# 05-ModuleControls.net
KiCad netlist of a schematic drawn in Altium Designer
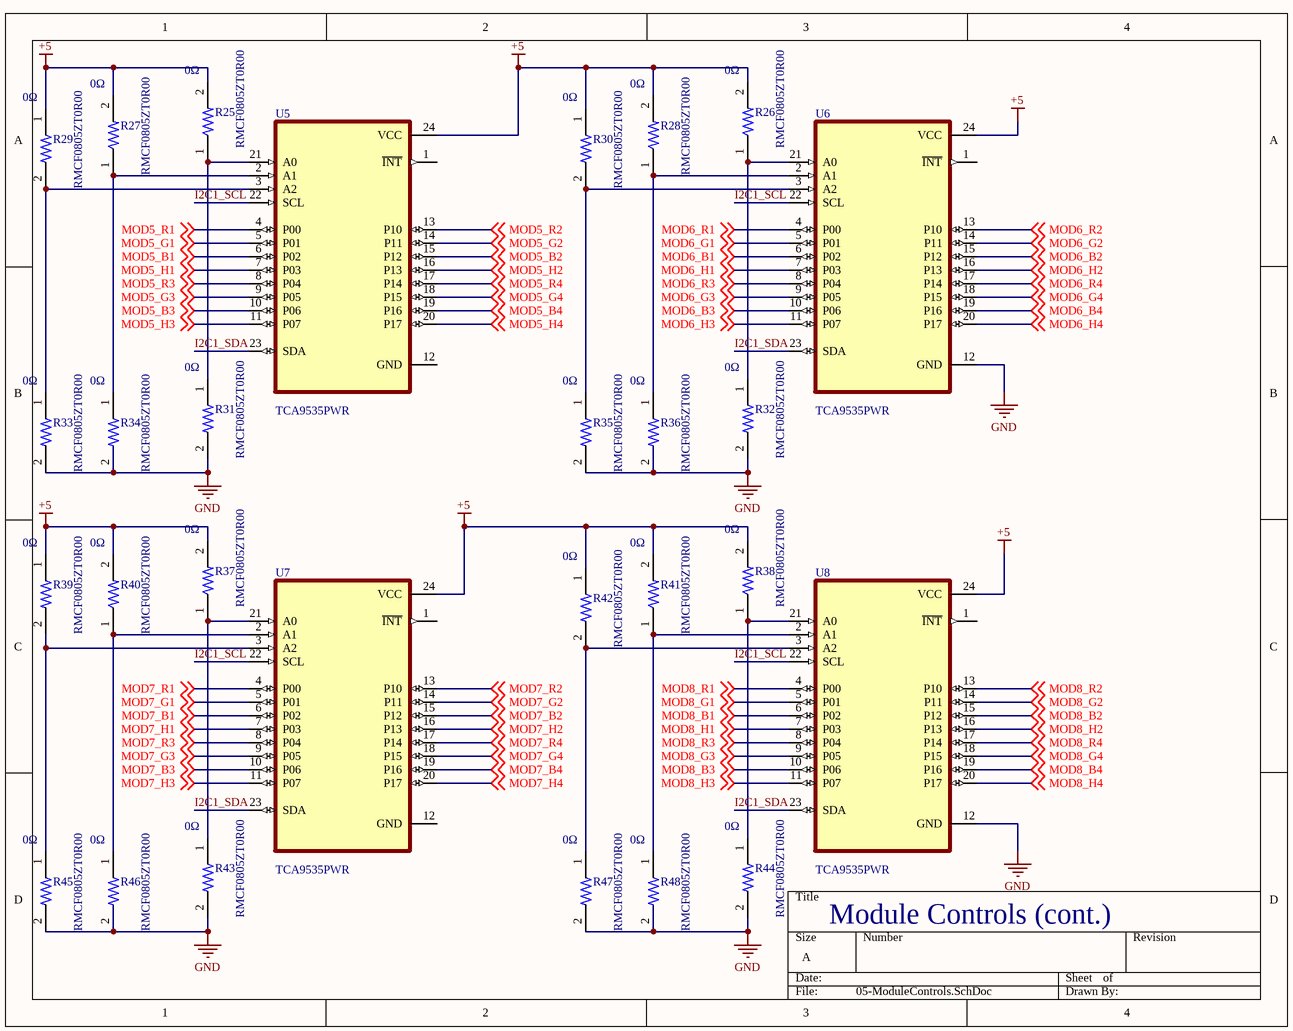
[diagram p0: 05-ModuleControls.SchDoc]

(export (version "E")
  (design (tool "Eeschema 10.0.6"))
  (components
    (comp (ref "R25")
      (value "RMCF0805ZT0R00")
      (footprint "RESC2012X60N")
      (description "0 Ohms Jumper 0.125W, 1/8W Chip Resistor 0805 (2012 Metric) Automotive AEC-Q200 Thick Film")
      (fields (field (name "MF") "Stackpole Electronics") (field (name "RESITANCE") "0Ω"))
      (libsource (lib "base-board") (part "RMCF0805ZT0R00"))
    )
    (comp (ref "R26")
      (value "RMCF0805ZT0R00")
      (footprint "RESC2012X60N")
      (description "0 Ohms Jumper 0.125W, 1/8W Chip Resistor 0805 (2012 Metric) Automotive AEC-Q200 Thick Film")
      (fields (field (name "MF") "Stackpole Electronics") (field (name "RESITANCE") "0Ω"))
      (libsource (lib "base-board") (part "RMCF0805ZT0R00"))
    )
    (comp (ref "R27")
      (value "RMCF0805ZT0R00")
      (footprint "RESC2012X60N")
      (description "0 Ohms Jumper 0.125W, 1/8W Chip Resistor 0805 (2012 Metric) Automotive AEC-Q200 Thick Film")
      (fields (field (name "MF") "Stackpole Electronics") (field (name "RESITANCE") "0Ω"))
      (libsource (lib "base-board") (part "RMCF0805ZT0R00"))
    )
    (comp (ref "R28")
      (value "RMCF0805ZT0R00")
      (footprint "RESC2012X60N")
      (description "0 Ohms Jumper 0.125W, 1/8W Chip Resistor 0805 (2012 Metric) Automotive AEC-Q200 Thick Film")
      (fields (field (name "MF") "Stackpole Electronics") (field (name "RESITANCE") "0Ω"))
      (libsource (lib "base-board") (part "RMCF0805ZT0R00"))
    )
    (comp (ref "R29")
      (value "RMCF0805ZT0R00")
      (footprint "RESC2012X60N")
      (description "0 Ohms Jumper 0.125W, 1/8W Chip Resistor 0805 (2012 Metric) Automotive AEC-Q200 Thick Film")
      (fields (field (name "MF") "Stackpole Electronics") (field (name "RESITANCE") "0Ω"))
      (libsource (lib "base-board") (part "RMCF0805ZT0R00"))
    )
    (comp (ref "R30")
      (value "RMCF0805ZT0R00")
      (footprint "RESC2012X60N")
      (description "0 Ohms Jumper 0.125W, 1/8W Chip Resistor 0805 (2012 Metric) Automotive AEC-Q200 Thick Film")
      (fields (field (name "MF") "Stackpole Electronics") (field (name "RESITANCE") "0Ω"))
      (libsource (lib "base-board") (part "RMCF0805ZT0R00"))
    )
    (comp (ref "R31")
      (value "RMCF0805ZT0R00")
      (footprint "RESC2012X60N")
      (description "0 Ohms Jumper 0.125W, 1/8W Chip Resistor 0805 (2012 Metric) Automotive AEC-Q200 Thick Film")
      (fields (field (name "MF") "Stackpole Electronics") (field (name "RESITANCE") "0Ω"))
      (libsource (lib "base-board") (part "RMCF0805ZT0R00"))
    )
    (comp (ref "R32")
      (value "RMCF0805ZT0R00")
      (footprint "RESC2012X60N")
      (description "0 Ohms Jumper 0.125W, 1/8W Chip Resistor 0805 (2012 Metric) Automotive AEC-Q200 Thick Film")
      (fields (field (name "MF") "Stackpole Electronics") (field (name "RESITANCE") "0Ω"))
      (libsource (lib "base-board") (part "RMCF0805ZT0R00"))
    )
    (comp (ref "R33")
      (value "RMCF0805ZT0R00")
      (footprint "RESC2012X60N")
      (description "0 Ohms Jumper 0.125W, 1/8W Chip Resistor 0805 (2012 Metric) Automotive AEC-Q200 Thick Film")
      (fields (field (name "MF") "Stackpole Electronics") (field (name "RESITANCE") "0Ω"))
      (libsource (lib "base-board") (part "RMCF0805ZT0R00"))
    )
    (comp (ref "R34")
      (value "RMCF0805ZT0R00")
      (footprint "RESC2012X60N")
      (description "0 Ohms Jumper 0.125W, 1/8W Chip Resistor 0805 (2012 Metric) Automotive AEC-Q200 Thick Film")
      (fields (field (name "MF") "Stackpole Electronics") (field (name "RESITANCE") "0Ω"))
      (libsource (lib "base-board") (part "RMCF0805ZT0R00"))
    )
    (comp (ref "R35")
      (value "RMCF0805ZT0R00")
      (footprint "RESC2012X60N")
      (description "0 Ohms Jumper 0.125W, 1/8W Chip Resistor 0805 (2012 Metric) Automotive AEC-Q200 Thick Film")
      (fields (field (name "MF") "Stackpole Electronics") (field (name "RESITANCE") "0Ω"))
      (libsource (lib "base-board") (part "RMCF0805ZT0R00"))
    )
    (comp (ref "R36")
      (value "RMCF0805ZT0R00")
      (footprint "RESC2012X60N")
      (description "0 Ohms Jumper 0.125W, 1/8W Chip Resistor 0805 (2012 Metric) Automotive AEC-Q200 Thick Film")
      (fields (field (name "MF") "Stackpole Electronics") (field (name "RESITANCE") "0Ω"))
      (libsource (lib "base-board") (part "RMCF0805ZT0R00"))
    )
    (comp (ref "R37")
      (value "RMCF0805ZT0R00")
      (footprint "RESC2012X60N")
      (description "0 Ohms Jumper 0.125W, 1/8W Chip Resistor 0805 (2012 Metric) Automotive AEC-Q200 Thick Film")
      (fields (field (name "MF") "Stackpole Electronics") (field (name "RESITANCE") "0Ω"))
      (libsource (lib "base-board") (part "RMCF0805ZT0R00"))
    )
    (comp (ref "R38")
      (value "RMCF0805ZT0R00")
      (footprint "RESC2012X60N")
      (description "0 Ohms Jumper 0.125W, 1/8W Chip Resistor 0805 (2012 Metric) Automotive AEC-Q200 Thick Film")
      (fields (field (name "MF") "Stackpole Electronics") (field (name "RESITANCE") "0Ω"))
      (libsource (lib "base-board") (part "RMCF0805ZT0R00"))
    )
    (comp (ref "R39")
      (value "RMCF0805ZT0R00")
      (footprint "RESC2012X60N")
      (description "0 Ohms Jumper 0.125W, 1/8W Chip Resistor 0805 (2012 Metric) Automotive AEC-Q200 Thick Film")
      (fields (field (name "MF") "Stackpole Electronics") (field (name "RESITANCE") "0Ω"))
      (libsource (lib "base-board") (part "RMCF0805ZT0R00"))
    )
    (comp (ref "R40")
      (value "RMCF0805ZT0R00")
      (footprint "RESC2012X60N")
      (description "0 Ohms Jumper 0.125W, 1/8W Chip Resistor 0805 (2012 Metric) Automotive AEC-Q200 Thick Film")
      (fields (field (name "MF") "Stackpole Electronics") (field (name "RESITANCE") "0Ω"))
      (libsource (lib "base-board") (part "RMCF0805ZT0R00"))
    )
    (comp (ref "R41")
      (value "RMCF0805ZT0R00")
      (footprint "RESC2012X60N")
      (description "0 Ohms Jumper 0.125W, 1/8W Chip Resistor 0805 (2012 Metric) Automotive AEC-Q200 Thick Film")
      (fields (field (name "MF") "Stackpole Electronics") (field (name "RESITANCE") "0Ω"))
      (libsource (lib "base-board") (part "RMCF0805ZT0R00"))
    )
    (comp (ref "R42")
      (value "RMCF0805ZT0R00")
      (footprint "RESC2012X60N")
      (description "0 Ohms Jumper 0.125W, 1/8W Chip Resistor 0805 (2012 Metric) Automotive AEC-Q200 Thick Film")
      (fields (field (name "MF") "Stackpole Electronics") (field (name "RESITANCE") "0Ω"))
      (libsource (lib "base-board") (part "RMCF0805ZT0R00"))
    )
    (comp (ref "R43")
      (value "RMCF0805ZT0R00")
      (footprint "RESC2012X60N")
      (description "0 Ohms Jumper 0.125W, 1/8W Chip Resistor 0805 (2012 Metric) Automotive AEC-Q200 Thick Film")
      (fields (field (name "MF") "Stackpole Electronics") (field (name "RESITANCE") "0Ω"))
      (libsource (lib "base-board") (part "RMCF0805ZT0R00"))
    )
    (comp (ref "R44")
      (value "RMCF0805ZT0R00")
      (footprint "RESC2012X60N")
      (description "0 Ohms Jumper 0.125W, 1/8W Chip Resistor 0805 (2012 Metric) Automotive AEC-Q200 Thick Film")
      (fields (field (name "MF") "Stackpole Electronics") (field (name "RESITANCE") "0Ω"))
      (libsource (lib "base-board") (part "RMCF0805ZT0R00"))
    )
    (comp (ref "R45")
      (value "RMCF0805ZT0R00")
      (footprint "RESC2012X60N")
      (description "0 Ohms Jumper 0.125W, 1/8W Chip Resistor 0805 (2012 Metric) Automotive AEC-Q200 Thick Film")
      (fields (field (name "MF") "Stackpole Electronics") (field (name "RESITANCE") "0Ω"))
      (libsource (lib "base-board") (part "RMCF0805ZT0R00"))
    )
    (comp (ref "R46")
      (value "RMCF0805ZT0R00")
      (footprint "RESC2012X60N")
      (description "0 Ohms Jumper 0.125W, 1/8W Chip Resistor 0805 (2012 Metric) Automotive AEC-Q200 Thick Film")
      (fields (field (name "MF") "Stackpole Electronics") (field (name "RESITANCE") "0Ω"))
      (libsource (lib "base-board") (part "RMCF0805ZT0R00"))
    )
    (comp (ref "R47")
      (value "RMCF0805ZT0R00")
      (footprint "RESC2012X60N")
      (description "0 Ohms Jumper 0.125W, 1/8W Chip Resistor 0805 (2012 Metric) Automotive AEC-Q200 Thick Film")
      (fields (field (name "MF") "Stackpole Electronics") (field (name "RESITANCE") "0Ω"))
      (libsource (lib "base-board") (part "RMCF0805ZT0R00"))
    )
    (comp (ref "R48")
      (value "RMCF0805ZT0R00")
      (footprint "RESC2012X60N")
      (description "0 Ohms Jumper 0.125W, 1/8W Chip Resistor 0805 (2012 Metric) Automotive AEC-Q200 Thick Film")
      (fields (field (name "MF") "Stackpole Electronics") (field (name "RESITANCE") "0Ω"))
      (libsource (lib "base-board") (part "RMCF0805ZT0R00"))
    )
    (comp (ref "U5")
      (value "TCA9535PWR")
      (footprint "SOP65P640X120-24N")
      (fields (field (name "MF") "Texas Instruments"))
      (libsource (lib "base-board") (part "TCA9535PWR"))
    )
    (comp (ref "U6")
      (value "TCA9535PWR")
      (footprint "SOP65P640X120-24N")
      (fields (field (name "MF") "Texas Instruments"))
      (libsource (lib "base-board") (part "TCA9535PWR"))
    )
    (comp (ref "U7")
      (value "TCA9535PWR")
      (footprint "SOP65P640X120-24N")
      (fields (field (name "MF") "Texas Instruments"))
      (libsource (lib "base-board") (part "TCA9535PWR"))
    )
    (comp (ref "U8")
      (value "TCA9535PWR")
      (footprint "SOP65P640X120-24N")
      (fields (field (name "MF") "Texas Instruments"))
      (libsource (lib "base-board") (part "TCA9535PWR"))
    )
  )
  (nets
    (net (code "1") (name "+5") (class "Default")
      (node (ref "R25") (pin "2") (pinfunction "2_2") (pintype "passive"))
      (node (ref "R26") (pin "2") (pinfunction "2_2") (pintype "passive"))
      (node (ref "R27") (pin "2") (pinfunction "2_2") (pintype "passive"))
      (node (ref "R28") (pin "2") (pinfunction "2_2") (pintype "passive"))
      (node (ref "R29") (pin "1") (pinfunction "1_1") (pintype "passive"))
      (node (ref "R30") (pin "1") (pinfunction "1_1") (pintype "passive"))
      (node (ref "R37") (pin "2") (pinfunction "2_2") (pintype "passive"))
      (node (ref "R38") (pin "2") (pinfunction "2_2") (pintype "passive"))
      (node (ref "R39") (pin "1") (pinfunction "1_1") (pintype "passive"))
      (node (ref "R40") (pin "2") (pinfunction "2_2") (pintype "passive"))
      (node (ref "R41") (pin "2") (pinfunction "2_2") (pintype "passive"))
      (node (ref "R42") (pin "1") (pinfunction "1_1") (pintype "passive"))
      (node (ref "U5") (pin "24") (pinfunction "VCC_24") (pintype "power_in"))
      (node (ref "U6") (pin "24") (pinfunction "VCC_24") (pintype "power_in"))
      (node (ref "U7") (pin "24") (pinfunction "VCC_24") (pintype "power_in"))
      (node (ref "U8") (pin "24") (pinfunction "VCC_24") (pintype "power_in"))
    )
    (net (code "2") (name "/I2C1_SCL") (class "Default")
      (node (ref "U5") (pin "22") (pinfunction "SCL_22") (pintype "input"))
      (node (ref "U6") (pin "22") (pinfunction "SCL_22") (pintype "input"))
      (node (ref "U7") (pin "22") (pinfunction "SCL_22") (pintype "input"))
      (node (ref "U8") (pin "22") (pinfunction "SCL_22") (pintype "input"))
    )
    (net (code "3") (name "/I2C1_SDA") (class "Default")
      (node (ref "U5") (pin "23") (pinfunction "SDA_23") (pintype "bidirectional"))
      (node (ref "U6") (pin "23") (pinfunction "SDA_23") (pintype "bidirectional"))
      (node (ref "U7") (pin "23") (pinfunction "SDA_23") (pintype "bidirectional"))
      (node (ref "U8") (pin "23") (pinfunction "SDA_23") (pintype "bidirectional"))
    )
    (net (code "4") (name "GND") (class "Default")
      (node (ref "R31") (pin "2") (pinfunction "2_2") (pintype "passive"))
      (node (ref "R32") (pin "2") (pinfunction "2_2") (pintype "passive"))
      (node (ref "R33") (pin "2") (pinfunction "2_2") (pintype "passive"))
      (node (ref "R34") (pin "2") (pinfunction "2_2") (pintype "passive"))
      (node (ref "R35") (pin "2") (pinfunction "2_2") (pintype "passive"))
      (node (ref "R36") (pin "2") (pinfunction "2_2") (pintype "passive"))
      (node (ref "R43") (pin "2") (pinfunction "2_2") (pintype "passive"))
      (node (ref "R44") (pin "2") (pinfunction "2_2") (pintype "passive"))
      (node (ref "R45") (pin "2") (pinfunction "2_2") (pintype "passive"))
      (node (ref "R46") (pin "2") (pinfunction "2_2") (pintype "passive"))
      (node (ref "R47") (pin "2") (pinfunction "2_2") (pintype "passive"))
      (node (ref "R48") (pin "2") (pinfunction "2_2") (pintype "passive"))
      (node (ref "U6") (pin "12") (pinfunction "GND_12") (pintype "power_in"))
      (node (ref "U8") (pin "12") (pinfunction "GND_12") (pintype "power_in"))
    )
    (net (code "5") (name "MOD5_B1") (class "Default")
      (node (ref "U5") (pin "6") (pinfunction "P02_6") (pintype "bidirectional"))
    )
    (net (code "6") (name "MOD5_B2") (class "Default")
      (node (ref "U5") (pin "15") (pinfunction "P12_15") (pintype "bidirectional"))
    )
    (net (code "7") (name "MOD5_B3") (class "Default")
      (node (ref "U5") (pin "10") (pinfunction "P06_10") (pintype "bidirectional"))
    )
    (net (code "8") (name "MOD5_B4") (class "Default")
      (node (ref "U5") (pin "19") (pinfunction "P16_19") (pintype "bidirectional"))
    )
    (net (code "9") (name "MOD5_G1") (class "Default")
      (node (ref "U5") (pin "5") (pinfunction "P01_5") (pintype "bidirectional"))
    )
    (net (code "10") (name "MOD5_G2") (class "Default")
      (node (ref "U5") (pin "14") (pinfunction "P11_14") (pintype "bidirectional"))
    )
    (net (code "11") (name "MOD5_G3") (class "Default")
      (node (ref "U5") (pin "9") (pinfunction "P05_9") (pintype "bidirectional"))
    )
    (net (code "12") (name "MOD5_G4") (class "Default")
      (node (ref "U5") (pin "18") (pinfunction "P15_18") (pintype "bidirectional"))
    )
    (net (code "13") (name "MOD5_H1") (class "Default")
      (node (ref "U5") (pin "7") (pinfunction "P03_7") (pintype "bidirectional"))
    )
    (net (code "14") (name "MOD5_H2") (class "Default")
      (node (ref "U5") (pin "16") (pinfunction "P13_16") (pintype "bidirectional"))
    )
    (net (code "15") (name "MOD5_H3") (class "Default")
      (node (ref "U5") (pin "11") (pinfunction "P07_11") (pintype "bidirectional"))
    )
    (net (code "16") (name "MOD5_H4") (class "Default")
      (node (ref "U5") (pin "20") (pinfunction "P17_20") (pintype "bidirectional"))
    )
    (net (code "17") (name "MOD5_R1") (class "Default")
      (node (ref "U5") (pin "4") (pinfunction "P00_4") (pintype "bidirectional"))
    )
    (net (code "18") (name "MOD5_R2") (class "Default")
      (node (ref "U5") (pin "13") (pinfunction "P10_13") (pintype "bidirectional"))
    )
    (net (code "19") (name "MOD5_R3") (class "Default")
      (node (ref "U5") (pin "8") (pinfunction "P04_8") (pintype "bidirectional"))
    )
    (net (code "20") (name "MOD5_R4") (class "Default")
      (node (ref "U5") (pin "17") (pinfunction "P14_17") (pintype "bidirectional"))
    )
    (net (code "21") (name "MOD6_B1") (class "Default")
      (node (ref "U6") (pin "6") (pinfunction "P02_6") (pintype "bidirectional"))
    )
    (net (code "22") (name "MOD6_B2") (class "Default")
      (node (ref "U6") (pin "15") (pinfunction "P12_15") (pintype "bidirectional"))
    )
    (net (code "23") (name "MOD6_B3") (class "Default")
      (node (ref "U6") (pin "10") (pinfunction "P06_10") (pintype "bidirectional"))
    )
    (net (code "24") (name "MOD6_B4") (class "Default")
      (node (ref "U6") (pin "19") (pinfunction "P16_19") (pintype "bidirectional"))
    )
    (net (code "25") (name "MOD6_G1") (class "Default")
      (node (ref "U6") (pin "5") (pinfunction "P01_5") (pintype "bidirectional"))
    )
    (net (code "26") (name "MOD6_G2") (class "Default")
      (node (ref "U6") (pin "14") (pinfunction "P11_14") (pintype "bidirectional"))
    )
    (net (code "27") (name "MOD6_G3") (class "Default")
      (node (ref "U6") (pin "9") (pinfunction "P05_9") (pintype "bidirectional"))
    )
    (net (code "28") (name "MOD6_G4") (class "Default")
      (node (ref "U6") (pin "18") (pinfunction "P15_18") (pintype "bidirectional"))
    )
    (net (code "29") (name "MOD6_H1") (class "Default")
      (node (ref "U6") (pin "7") (pinfunction "P03_7") (pintype "bidirectional"))
    )
    (net (code "30") (name "MOD6_H2") (class "Default")
      (node (ref "U6") (pin "16") (pinfunction "P13_16") (pintype "bidirectional"))
    )
    (net (code "31") (name "MOD6_H3") (class "Default")
      (node (ref "U6") (pin "11") (pinfunction "P07_11") (pintype "bidirectional"))
    )
    (net (code "32") (name "MOD6_H4") (class "Default")
      (node (ref "U6") (pin "20") (pinfunction "P17_20") (pintype "bidirectional"))
    )
    (net (code "33") (name "MOD6_R1") (class "Default")
      (node (ref "U6") (pin "4") (pinfunction "P00_4") (pintype "bidirectional"))
    )
    (net (code "34") (name "MOD6_R2") (class "Default")
      (node (ref "U6") (pin "13") (pinfunction "P10_13") (pintype "bidirectional"))
    )
    (net (code "35") (name "MOD6_R3") (class "Default")
      (node (ref "U6") (pin "8") (pinfunction "P04_8") (pintype "bidirectional"))
    )
    (net (code "36") (name "MOD6_R4") (class "Default")
      (node (ref "U6") (pin "17") (pinfunction "P14_17") (pintype "bidirectional"))
    )
    (net (code "37") (name "MOD7_B1") (class "Default")
      (node (ref "U7") (pin "6") (pinfunction "P02_6") (pintype "bidirectional"))
    )
    (net (code "38") (name "MOD7_B2") (class "Default")
      (node (ref "U7") (pin "15") (pinfunction "P12_15") (pintype "bidirectional"))
    )
    (net (code "39") (name "MOD7_B3") (class "Default")
      (node (ref "U7") (pin "10") (pinfunction "P06_10") (pintype "bidirectional"))
    )
    (net (code "40") (name "MOD7_B4") (class "Default")
      (node (ref "U7") (pin "19") (pinfunction "P16_19") (pintype "bidirectional"))
    )
    (net (code "41") (name "MOD7_G1") (class "Default")
      (node (ref "U7") (pin "5") (pinfunction "P01_5") (pintype "bidirectional"))
    )
    (net (code "42") (name "MOD7_G2") (class "Default")
      (node (ref "U7") (pin "14") (pinfunction "P11_14") (pintype "bidirectional"))
    )
    (net (code "43") (name "MOD7_G3") (class "Default")
      (node (ref "U7") (pin "9") (pinfunction "P05_9") (pintype "bidirectional"))
    )
    (net (code "44") (name "MOD7_G4") (class "Default")
      (node (ref "U7") (pin "18") (pinfunction "P15_18") (pintype "bidirectional"))
    )
    (net (code "45") (name "MOD7_H1") (class "Default")
      (node (ref "U7") (pin "7") (pinfunction "P03_7") (pintype "bidirectional"))
    )
    (net (code "46") (name "MOD7_H2") (class "Default")
      (node (ref "U7") (pin "16") (pinfunction "P13_16") (pintype "bidirectional"))
    )
    (net (code "47") (name "MOD7_H3") (class "Default")
      (node (ref "U7") (pin "11") (pinfunction "P07_11") (pintype "bidirectional"))
    )
    (net (code "48") (name "MOD7_H4") (class "Default")
      (node (ref "U7") (pin "20") (pinfunction "P17_20") (pintype "bidirectional"))
    )
    (net (code "49") (name "MOD7_R1") (class "Default")
      (node (ref "U7") (pin "4") (pinfunction "P00_4") (pintype "bidirectional"))
    )
    (net (code "50") (name "MOD7_R2") (class "Default")
      (node (ref "U7") (pin "13") (pinfunction "P10_13") (pintype "bidirectional"))
    )
    (net (code "51") (name "MOD7_R3") (class "Default")
      (node (ref "U7") (pin "8") (pinfunction "P04_8") (pintype "bidirectional"))
    )
    (net (code "52") (name "MOD7_R4") (class "Default")
      (node (ref "U7") (pin "17") (pinfunction "P14_17") (pintype "bidirectional"))
    )
    (net (code "53") (name "MOD8_B1") (class "Default")
      (node (ref "U8") (pin "6") (pinfunction "P02_6") (pintype "bidirectional"))
    )
    (net (code "54") (name "MOD8_B2") (class "Default")
      (node (ref "U8") (pin "15") (pinfunction "P12_15") (pintype "bidirectional"))
    )
    (net (code "55") (name "MOD8_B3") (class "Default")
      (node (ref "U8") (pin "10") (pinfunction "P06_10") (pintype "bidirectional"))
    )
    (net (code "56") (name "MOD8_B4") (class "Default")
      (node (ref "U8") (pin "19") (pinfunction "P16_19") (pintype "bidirectional"))
    )
    (net (code "57") (name "MOD8_G1") (class "Default")
      (node (ref "U8") (pin "5") (pinfunction "P01_5") (pintype "bidirectional"))
    )
    (net (code "58") (name "MOD8_G2") (class "Default")
      (node (ref "U8") (pin "14") (pinfunction "P11_14") (pintype "bidirectional"))
    )
    (net (code "59") (name "MOD8_G3") (class "Default")
      (node (ref "U8") (pin "9") (pinfunction "P05_9") (pintype "bidirectional"))
    )
    (net (code "60") (name "MOD8_G4") (class "Default")
      (node (ref "U8") (pin "18") (pinfunction "P15_18") (pintype "bidirectional"))
    )
    (net (code "61") (name "MOD8_H1") (class "Default")
      (node (ref "U8") (pin "7") (pinfunction "P03_7") (pintype "bidirectional"))
    )
    (net (code "62") (name "MOD8_H2") (class "Default")
      (node (ref "U8") (pin "16") (pinfunction "P13_16") (pintype "bidirectional"))
    )
    (net (code "63") (name "MOD8_H3") (class "Default")
      (node (ref "U8") (pin "11") (pinfunction "P07_11") (pintype "bidirectional"))
    )
    (net (code "64") (name "MOD8_H4") (class "Default")
      (node (ref "U8") (pin "20") (pinfunction "P17_20") (pintype "bidirectional"))
    )
    (net (code "65") (name "MOD8_R1") (class "Default")
      (node (ref "U8") (pin "4") (pinfunction "P00_4") (pintype "bidirectional"))
    )
    (net (code "66") (name "MOD8_R2") (class "Default")
      (node (ref "U8") (pin "13") (pinfunction "P10_13") (pintype "bidirectional"))
    )
    (net (code "67") (name "MOD8_R3") (class "Default")
      (node (ref "U8") (pin "8") (pinfunction "P04_8") (pintype "bidirectional"))
    )
    (net (code "68") (name "MOD8_R4") (class "Default")
      (node (ref "U8") (pin "17") (pinfunction "P14_17") (pintype "bidirectional"))
    )
    (net (code "69") (name "Net-(U5-A0)") (class "Default")
      (node (ref "R25") (pin "1") (pinfunction "1_1") (pintype "passive"))
      (node (ref "R31") (pin "1") (pinfunction "1_1") (pintype "passive"))
      (node (ref "U5") (pin "21") (pinfunction "A0_21") (pintype "input"))
    )
    (net (code "70") (name "Net-(U5-A1)") (class "Default")
      (node (ref "R27") (pin "1") (pinfunction "1_1") (pintype "passive"))
      (node (ref "R34") (pin "1") (pinfunction "1_1") (pintype "passive"))
      (node (ref "U5") (pin "2") (pinfunction "A1_2") (pintype "input"))
    )
    (net (code "71") (name "Net-(U5-A2)") (class "Default")
      (node (ref "R29") (pin "2") (pinfunction "2_2") (pintype "passive"))
      (node (ref "R33") (pin "1") (pinfunction "1_1") (pintype "passive"))
      (node (ref "U5") (pin "3") (pinfunction "A2_3") (pintype "input"))
    )
    (net (code "72") (name "Net-(U6-A0)") (class "Default")
      (node (ref "R26") (pin "1") (pinfunction "1_1") (pintype "passive"))
      (node (ref "R32") (pin "1") (pinfunction "1_1") (pintype "passive"))
      (node (ref "U6") (pin "21") (pinfunction "A0_21") (pintype "input"))
    )
    (net (code "73") (name "Net-(U6-A1)") (class "Default")
      (node (ref "R28") (pin "1") (pinfunction "1_1") (pintype "passive"))
      (node (ref "R36") (pin "1") (pinfunction "1_1") (pintype "passive"))
      (node (ref "U6") (pin "2") (pinfunction "A1_2") (pintype "input"))
    )
    (net (code "74") (name "Net-(U6-A2)") (class "Default")
      (node (ref "R30") (pin "2") (pinfunction "2_2") (pintype "passive"))
      (node (ref "R35") (pin "1") (pinfunction "1_1") (pintype "passive"))
      (node (ref "U6") (pin "3") (pinfunction "A2_3") (pintype "input"))
    )
    (net (code "75") (name "Net-(U7-A0)") (class "Default")
      (node (ref "R37") (pin "1") (pinfunction "1_1") (pintype "passive"))
      (node (ref "R43") (pin "1") (pinfunction "1_1") (pintype "passive"))
      (node (ref "U7") (pin "21") (pinfunction "A0_21") (pintype "input"))
    )
    (net (code "76") (name "Net-(U7-A1)") (class "Default")
      (node (ref "R40") (pin "1") (pinfunction "1_1") (pintype "passive"))
      (node (ref "R46") (pin "1") (pinfunction "1_1") (pintype "passive"))
      (node (ref "U7") (pin "2") (pinfunction "A1_2") (pintype "input"))
    )
    (net (code "77") (name "Net-(U7-A2)") (class "Default")
      (node (ref "R39") (pin "2") (pinfunction "2_2") (pintype "passive"))
      (node (ref "R45") (pin "1") (pinfunction "1_1") (pintype "passive"))
      (node (ref "U7") (pin "3") (pinfunction "A2_3") (pintype "input"))
    )
    (net (code "78") (name "Net-(U8-A0)") (class "Default")
      (node (ref "R38") (pin "1") (pinfunction "1_1") (pintype "passive"))
      (node (ref "R44") (pin "1") (pinfunction "1_1") (pintype "passive"))
      (node (ref "U8") (pin "21") (pinfunction "A0_21") (pintype "input"))
    )
    (net (code "79") (name "Net-(U8-A1)") (class "Default")
      (node (ref "R41") (pin "1") (pinfunction "1_1") (pintype "passive"))
      (node (ref "R48") (pin "1") (pinfunction "1_1") (pintype "passive"))
      (node (ref "U8") (pin "2") (pinfunction "A1_2") (pintype "input"))
    )
    (net (code "80") (name "Net-(U8-A2)") (class "Default")
      (node (ref "R42") (pin "2") (pinfunction "2_2") (pintype "passive"))
      (node (ref "R47") (pin "1") (pinfunction "1_1") (pintype "passive"))
      (node (ref "U8") (pin "3") (pinfunction "A2_3") (pintype "input"))
    )
    (net (code "81") (name "unconnected-(U5-GND-Pad12)") (class "Default")
      (node (ref "U5") (pin "12") (pinfunction "GND_12") (pintype "power_in"))
    )
    (net (code "82") (name "unconnected-(U5-~{INT}-Pad1)") (class "Default")
      (node (ref "U5") (pin "1") (pinfunction "~{INT}_1") (pintype "output"))
    )
    (net (code "83") (name "unconnected-(U6-~{INT}-Pad1)") (class "Default")
      (node (ref "U6") (pin "1") (pinfunction "~{INT}_1") (pintype "output"))
    )
    (net (code "84") (name "unconnected-(U7-GND-Pad12)") (class "Default")
      (node (ref "U7") (pin "12") (pinfunction "GND_12") (pintype "power_in"))
    )
    (net (code "85") (name "unconnected-(U7-~{INT}-Pad1)") (class "Default")
      (node (ref "U7") (pin "1") (pinfunction "~{INT}_1") (pintype "output"))
    )
    (net (code "86") (name "unconnected-(U8-~{INT}-Pad1)") (class "Default")
      (node (ref "U8") (pin "1") (pinfunction "~{INT}_1") (pintype "output"))
    )
  )
)
